# opaq_n1.net
KiCad netlist of a schematic drawn in EAGLE
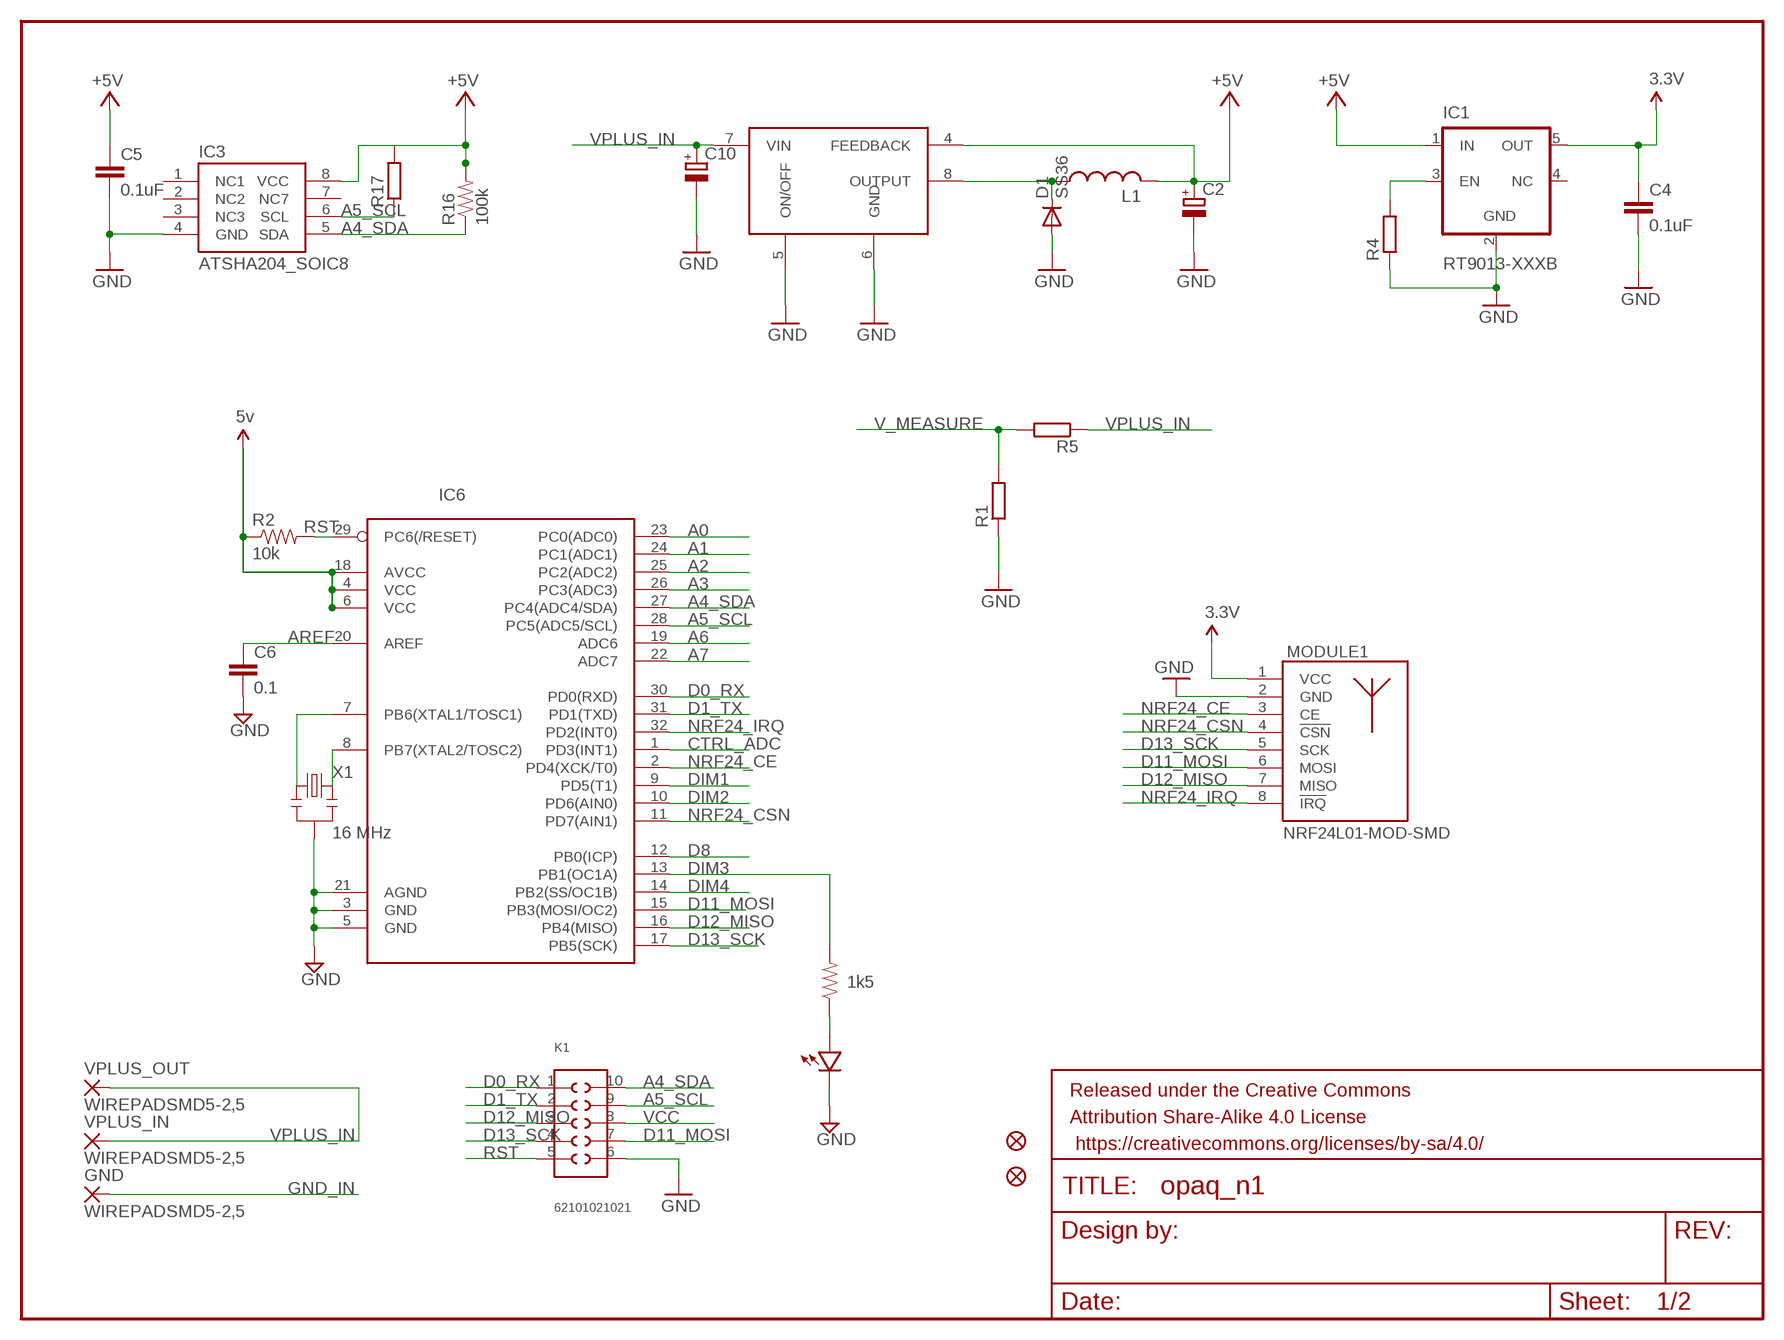
[diagram p0: schematic, sheet 1]
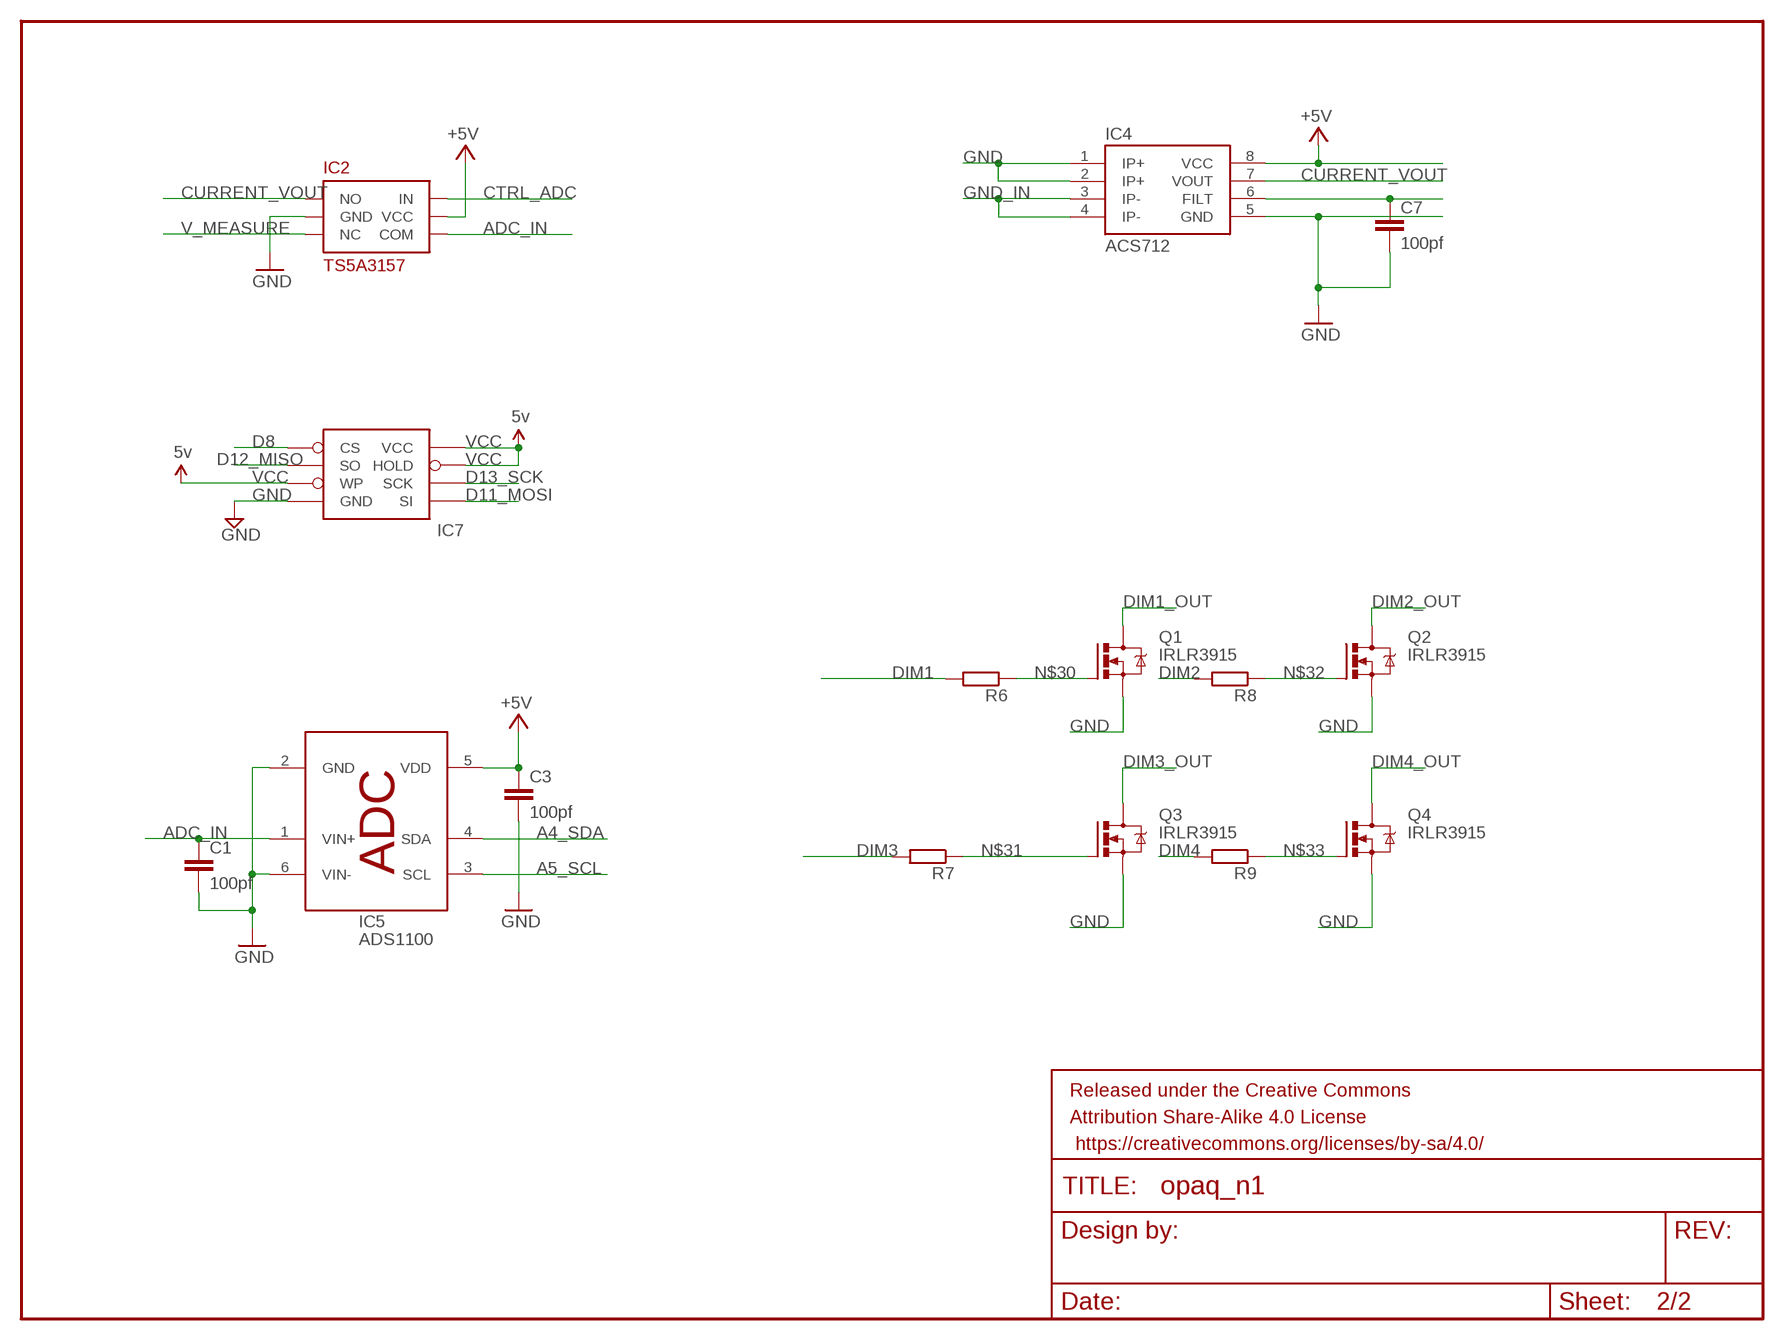
[diagram p1: schematic, sheet 2]

(export (version "E")
  (design (tool "Eeschema 10.0.6"))
  (components
    (comp (ref "C1")
      (value "100pf")
      (footprint "eagle-import:0402-CAP")
      (libsource (lib "eagle-import") (part "SparkFun-Passives_CAP0402-CAP"))
    )
    (comp (ref "C3")
      (value "100pf")
      (footprint "eagle-import:0402-CAP")
      (libsource (lib "eagle-import") (part "SparkFun-Passives_CAP0402-CAP"))
    )
    (comp (ref "C7")
      (value "100pf")
      (footprint "eagle-import:0402-CAP")
      (libsource (lib "eagle-import") (part "SparkFun-Passives_CAP0402-CAP"))
    )
    (comp (ref "FRAME2")
      (value "FRAME-LETTERNO_PACKAGE")
      (footprint "eagle-import:DUMMY")
      (fields (field (name "DESIGNER") "Nobody"))
      (libsource (lib "eagle-import") (part "FRAME-LETTERNO_PACKAGE"))
    )
    (comp (ref "IC2")
      (value "TS5A3157")
      (footprint "eagle-import:SOT23-6")
      (libsource (lib "eagle-import") (part "TS5A3157"))
    )
    (comp (ref "IC4")
      (value "ACS712")
      (footprint "eagle-import:SO08")
      (libsource (lib "eagle-import") (part "ACS712"))
    )
    (comp (ref "IC5")
      (value "ADS1100")
      (footprint "eagle-import:SOT23-6")
      (fields (field (name "MF") "TI"))
      (libsource (lib "eagle-import") (part "ADS1100"))
    )
    (comp (ref "IC7")
      (value "AT25F512BWIDE_5.3MM")
      (footprint "eagle-import:SO08WIDE")
      (libsource (lib "eagle-import") (part "AT25F512BWIDE_5.3MM"))
    )
    (comp (ref "Q1")
      (value "IRLR3915")
      (footprint "eagle-import:D-PAK_TO252AA")
      (libsource (lib "eagle-import") (part "IRLR3915"))
    )
    (comp (ref "Q2")
      (value "IRLR3915")
      (footprint "eagle-import:D-PAK_TO252AA")
      (libsource (lib "eagle-import") (part "IRLR3915"))
    )
    (comp (ref "Q3")
      (value "IRLR3915")
      (footprint "eagle-import:D-PAK_TO252AA")
      (libsource (lib "eagle-import") (part "IRLR3915"))
    )
    (comp (ref "Q4")
      (value "IRLR3915")
      (footprint "eagle-import:D-PAK_TO252AA")
      (libsource (lib "eagle-import") (part "IRLR3915"))
    )
    (comp (ref "R6")
      (value "R-EU_R0805")
      (footprint "eagle-import:0805")
      (libsource (lib "eagle-import") (part "R-EU_R0805"))
    )
    (comp (ref "R7")
      (value "R-EU_R0805")
      (footprint "eagle-import:0805")
      (libsource (lib "eagle-import") (part "R-EU_R0805"))
    )
    (comp (ref "R8")
      (value "R-EU_R0805")
      (footprint "eagle-import:0805")
      (libsource (lib "eagle-import") (part "R-EU_R0805"))
    )
    (comp (ref "R9")
      (value "R-EU_R0805")
      (footprint "eagle-import:0805")
      (libsource (lib "eagle-import") (part "R-EU_R0805"))
    )
    (comp (ref "C2")
      (value "CPOL-EUC/6032-28R")
      (footprint "eagle-import:C_6032-28R")
      (libsource (lib "eagle-import") (part "CPOL-EUC/6032-28R"))
    )
    (comp (ref "C4")
      (value "0.1uF")
      (footprint "eagle-import:0805")
      (libsource (lib "eagle-import") (part "SparkFun-Passives_CAP0805"))
    )
    (comp (ref "C5")
      (value "0.1uF")
      (footprint "eagle-import:0805")
      (libsource (lib "eagle-import") (part "SparkFun-Passives_CAP0805"))
    )
    (comp (ref "C6")
      (value "0.1")
      (footprint "eagle-import:0603-CAP")
      (libsource (lib "eagle-import") (part "CAP0603-CAP"))
    )
    (comp (ref "C10")
      (value "CPOL-EUD/7343-31R")
      (footprint "eagle-import:D_7343-31R")
      (libsource (lib "eagle-import") (part "CPOL-EUD/7343-31R"))
    )
    (comp (ref "D1")
      (value "SS36")
      (footprint "eagle-import:SMA-DIODE")
      (libsource (lib "eagle-import") (part "DIODESMA"))
    )
    (comp (ref "DIM")
      (value "LED0603")
      (footprint "eagle-import:0603-LED")
      (libsource (lib "eagle-import") (part "LED0603"))
    )
    (comp (ref "FRAME1")
      (value "FRAME-LETTER")
      (footprint "eagle-import:CREATIVE_COMMONS")
      (libsource (lib "eagle-import") (part "FRAME-LETTER"))
    )
    (comp (ref "GND")
      (value "WIREPADSMD5-2,5")
      (footprint "eagle-import:5-2,5")
      (libsource (lib "eagle-import") (part "WIREPADSMD5-2,5"))
    )
    (comp (ref "IC1")
      (value "RT9013-XXXB")
      (footprint "eagle-import:SOT23-5")
      (libsource (lib "eagle-import") (part "RT9013-XXXB"))
    )
    (comp (ref "IC3")
      (value "ATSHA204_SOIC8")
      (footprint "eagle-import:SOIC8")
      (libsource (lib "eagle-import") (part "ATSHA204_SOIC8"))
    )
    (comp (ref "IC6")
      (value "ATMega-328")
      (footprint "eagle-import:MLF32")
      (libsource (lib "eagle-import") (part "ATMEGA168/328MLF"))
    )
    (comp (ref "IC8")
      (value "LM2594HV")
      (footprint "eagle-import:SO08")
      (libsource (lib "eagle-import") (part "LM2594"))
    )
    (comp (ref "JP1")
      (value "FIDUCIAL1X2.5")
      (footprint "eagle-import:FIDUCIAL-1X2.5")
      (libsource (lib "eagle-import") (part "FIDUCIAL1X2.5"))
    )
    (comp (ref "JP2")
      (value "FIDUCIAL1X2.5")
      (footprint "eagle-import:FIDUCIAL-1X2.5")
      (libsource (lib "eagle-import") (part "FIDUCIAL1X2.5"))
    )
    (comp (ref "K1")
      (value "62101021021")
      (footprint "eagle-import:62101021021")
      (libsource (lib "eagle-import") (part "62101021021"))
    )
    (comp (ref "L1")
      (value "NR6045")
      (footprint "eagle-import:2525")
      (libsource (lib "eagle-import") (part "NR6045"))
    )
    (comp (ref "MODULE1")
      (value "NRF24L01-MOD-SMD")
      (footprint "eagle-import:SMD8-MODULE")
      (libsource (lib "eagle-import") (part "NRF24L01-MOD-SMD"))
    )
    (comp (ref "R1")
      (value "R-EU_R0805")
      (footprint "eagle-import:0805")
      (libsource (lib "eagle-import") (part "R-EU_R0805"))
    )
    (comp (ref "R2")
      (value "10k")
      (footprint "eagle-import:0603-RES")
      (libsource (lib "eagle-import") (part "RESISTOR0603-RES"))
    )
    (comp (ref "R3")
      (value "1k5")
      (footprint "eagle-import:0603-RES")
      (libsource (lib "eagle-import") (part "RESISTOR0603-RES"))
    )
    (comp (ref "R4")
      (value "R-EU_R0805")
      (footprint "eagle-import:0805")
      (libsource (lib "eagle-import") (part "R-EU_R0805"))
    )
    (comp (ref "R5")
      (value "R-EU_R0805")
      (footprint "eagle-import:0805")
      (libsource (lib "eagle-import") (part "R-EU_R0805"))
    )
    (comp (ref "R16")
      (value "100k")
      (footprint "eagle-import:0805")
      (libsource (lib "eagle-import") (part "SparkFun-Passives_RESISTOR0805-RES"))
    )
    (comp (ref "R17")
      (value "R-EU_R0805")
      (footprint "eagle-import:0805")
      (libsource (lib "eagle-import") (part "R-EU_R0805"))
    )
    (comp (ref "VPLUS_IN")
      (value "WIREPADSMD5-2,5")
      (footprint "eagle-import:5-2,5")
      (libsource (lib "eagle-import") (part "WIREPADSMD5-2,5"))
    )
    (comp (ref "VPLUS_OUT")
      (value "WIREPADSMD5-2,5")
      (footprint "eagle-import:5-2,5")
      (libsource (lib "eagle-import") (part "WIREPADSMD5-2,5"))
    )
    (comp (ref "X1")
      (value "16 MHz")
      (footprint "eagle-import:RESONATOR-SMD")
      (libsource (lib "eagle-import") (part "RESONATORSMD"))
    )
  )
  (nets
    (net (code "1") (name "+5V") (class "Default")
      (node (ref "C2") (pin "+") (pinfunction "+_+") (pintype "passive"))
      (node (ref "C3") (pin "1") (pinfunction "1_1") (pintype "passive"))
      (node (ref "C5") (pin "1") (pinfunction "1_1") (pintype "passive"))
      (node (ref "IC1") (pin "1") (pinfunction "IN_1") (pintype "input"))
      (node (ref "IC2") (pin "5") (pinfunction "VCC_5") (pintype "bidirectional"))
      (node (ref "IC3") (pin "8") (pinfunction "VCC_8") (pintype "power_in"))
      (node (ref "IC4") (pin "8") (pinfunction "VCC_8") (pintype "bidirectional"))
      (node (ref "IC5") (pin "5") (pinfunction "VDD_5") (pintype "power_in"))
      (node (ref "IC8") (pin "4") (pinfunction "FEEDBACK_4") (pintype "bidirectional"))
      (node (ref "L1") (pin "P$1") (pinfunction "P$1_P$1") (pintype "passive"))
      (node (ref "R16") (pin "2") (pinfunction "2_2") (pintype "passive"))
      (node (ref "R17") (pin "2") (pinfunction "2_2") (pintype "passive"))
    )
    (net (code "2") (name "3.3V") (class "Default")
      (node (ref "C4") (pin "1") (pinfunction "1_1") (pintype "passive"))
      (node (ref "IC1") (pin "5") (pinfunction "OUT_5") (pintype "passive"))
      (node (ref "MODULE1") (pin "1") (pinfunction "VCC_1") (pintype "power_in"))
    )
    (net (code "3") (name "A0") (class "Default")
      (node (ref "IC6") (pin "23") (pinfunction "PC0(ADC0)_23") (pintype "bidirectional"))
    )
    (net (code "4") (name "A1") (class "Default")
      (node (ref "IC6") (pin "24") (pinfunction "PC1(ADC1)_24") (pintype "bidirectional"))
    )
    (net (code "5") (name "A2") (class "Default")
      (node (ref "IC6") (pin "25") (pinfunction "PC2(ADC2)_25") (pintype "bidirectional"))
    )
    (net (code "6") (name "A3") (class "Default")
      (node (ref "IC6") (pin "26") (pinfunction "PC3(ADC3)_26") (pintype "bidirectional"))
    )
    (net (code "7") (name "A4_SDA") (class "Default")
      (node (ref "IC3") (pin "5") (pinfunction "SDA_5") (pintype "bidirectional"))
      (node (ref "IC5") (pin "4") (pinfunction "SDA_4") (pintype "bidirectional"))
      (node (ref "IC6") (pin "27") (pinfunction "PC4(ADC4/SDA)_27") (pintype "bidirectional"))
      (node (ref "K1") (pin "10") (pinfunction "10_10") (pintype "passive"))
      (node (ref "R16") (pin "1") (pinfunction "1_1") (pintype "passive"))
    )
    (net (code "8") (name "A5_SCL") (class "Default")
      (node (ref "IC3") (pin "6") (pinfunction "SCL_6") (pintype "bidirectional"))
      (node (ref "IC5") (pin "3") (pinfunction "SCL_3") (pintype "input"))
      (node (ref "IC6") (pin "28") (pinfunction "PC5(ADC5/SCL)_28") (pintype "bidirectional"))
      (node (ref "K1") (pin "9") (pinfunction "9_9") (pintype "passive"))
      (node (ref "R17") (pin "1") (pinfunction "1_1") (pintype "passive"))
    )
    (net (code "9") (name "A6") (class "Default")
      (node (ref "IC6") (pin "19") (pinfunction "ADC6_19") (pintype "bidirectional"))
    )
    (net (code "10") (name "A7") (class "Default")
      (node (ref "IC6") (pin "22") (pinfunction "ADC7_22") (pintype "bidirectional"))
    )
    (net (code "11") (name "ADC_IN") (class "Default")
      (node (ref "C1") (pin "1") (pinfunction "1_1") (pintype "passive"))
      (node (ref "IC2") (pin "4") (pinfunction "COM_4") (pintype "bidirectional"))
      (node (ref "IC5") (pin "1") (pinfunction "VIN+_1") (pintype "input"))
    )
    (net (code "12") (name "AREF") (class "Default")
      (node (ref "C6") (pin "1") (pinfunction "1_1") (pintype "passive"))
      (node (ref "IC6") (pin "20") (pinfunction "AREF_20") (pintype "bidirectional"))
    )
    (net (code "13") (name "CTRL_ADC") (class "Default")
      (node (ref "IC2") (pin "6") (pinfunction "IN_6") (pintype "bidirectional"))
      (node (ref "IC6") (pin "1") (pinfunction "PD3(INT1)_1") (pintype "bidirectional"))
    )
    (net (code "14") (name "CURRENT_VOUT") (class "Default")
      (node (ref "IC2") (pin "1") (pinfunction "NO_1") (pintype "bidirectional"))
      (node (ref "IC4") (pin "7") (pinfunction "VOUT_7") (pintype "bidirectional"))
    )
    (net (code "15") (name "D0_RX") (class "Default")
      (node (ref "IC6") (pin "30") (pinfunction "PD0(RXD)_30") (pintype "bidirectional"))
      (node (ref "K1") (pin "1") (pinfunction "1_1") (pintype "passive"))
    )
    (net (code "16") (name "D1_TX") (class "Default")
      (node (ref "IC6") (pin "31") (pinfunction "PD1(TXD)_31") (pintype "bidirectional"))
      (node (ref "K1") (pin "2") (pinfunction "2_2") (pintype "passive"))
    )
    (net (code "17") (name "D8") (class "Default")
      (node (ref "IC6") (pin "12") (pinfunction "PB0(ICP)_12") (pintype "bidirectional"))
      (node (ref "IC7") (pin "1") (pinfunction "CS_1") (pintype "bidirectional"))
    )
    (net (code "18") (name "D11_MOSI") (class "Default")
      (node (ref "IC6") (pin "15") (pinfunction "PB3(MOSI/OC2)_15") (pintype "bidirectional"))
      (node (ref "IC7") (pin "5") (pinfunction "SI_5") (pintype "bidirectional"))
      (node (ref "K1") (pin "7") (pinfunction "7_7") (pintype "passive"))
      (node (ref "MODULE1") (pin "6") (pinfunction "MOSI_6") (pintype "input"))
    )
    (net (code "19") (name "D12_MISO") (class "Default")
      (node (ref "IC6") (pin "16") (pinfunction "PB4(MISO)_16") (pintype "bidirectional"))
      (node (ref "IC7") (pin "2") (pinfunction "SO_2") (pintype "bidirectional"))
      (node (ref "K1") (pin "3") (pinfunction "3_3") (pintype "passive"))
      (node (ref "MODULE1") (pin "7") (pinfunction "MISO_7") (pintype "output"))
    )
    (net (code "20") (name "D13_SCK") (class "Default")
      (node (ref "IC6") (pin "17") (pinfunction "PB5(SCK)_17") (pintype "bidirectional"))
      (node (ref "IC7") (pin "6") (pinfunction "SCK_6") (pintype "bidirectional"))
      (node (ref "K1") (pin "4") (pinfunction "4_4") (pintype "passive"))
      (node (ref "MODULE1") (pin "5") (pinfunction "SCK_5") (pintype "input"))
    )
    (net (code "21") (name "DIM1") (class "Default")
      (node (ref "IC6") (pin "9") (pinfunction "PD5(T1)_9") (pintype "bidirectional"))
      (node (ref "R6") (pin "2") (pinfunction "2_2") (pintype "passive"))
    )
    (net (code "22") (name "DIM1_OUT") (class "Default")
      (node (ref "Q1") (pin "4") (pinfunction "D_4") (pintype "passive"))
    )
    (net (code "23") (name "DIM2") (class "Default")
      (node (ref "IC6") (pin "10") (pinfunction "PD6(AIN0)_10") (pintype "bidirectional"))
      (node (ref "R8") (pin "2") (pinfunction "2_2") (pintype "passive"))
    )
    (net (code "24") (name "DIM2_OUT") (class "Default")
      (node (ref "Q2") (pin "4") (pinfunction "D_4") (pintype "passive"))
    )
    (net (code "25") (name "DIM3") (class "Default")
      (node (ref "IC6") (pin "13") (pinfunction "PB1(OC1A)_13") (pintype "bidirectional"))
      (node (ref "R3") (pin "2") (pinfunction "2_2") (pintype "passive"))
      (node (ref "R7") (pin "2") (pinfunction "2_2") (pintype "passive"))
    )
    (net (code "26") (name "DIM3_OUT") (class "Default")
      (node (ref "Q3") (pin "4") (pinfunction "D_4") (pintype "passive"))
    )
    (net (code "27") (name "DIM4") (class "Default")
      (node (ref "IC6") (pin "14") (pinfunction "PB2(SS/OC1B)_14") (pintype "bidirectional"))
      (node (ref "R9") (pin "2") (pinfunction "2_2") (pintype "passive"))
    )
    (net (code "28") (name "DIM4_OUT") (class "Default")
      (node (ref "Q4") (pin "4") (pinfunction "D_4") (pintype "passive"))
    )
    (net (code "29") (name "GND") (class "Default")
      (node (ref "C1") (pin "2") (pinfunction "2_2") (pintype "passive"))
      (node (ref "C10") (pin "-") (pinfunction "-_-") (pintype "passive"))
      (node (ref "C2") (pin "-") (pinfunction "-_-") (pintype "passive"))
      (node (ref "C3") (pin "2") (pinfunction "2_2") (pintype "passive"))
      (node (ref "C4") (pin "2") (pinfunction "2_2") (pintype "passive"))
      (node (ref "C5") (pin "2") (pinfunction "2_2") (pintype "passive"))
      (node (ref "C6") (pin "2") (pinfunction "2_2") (pintype "passive"))
      (node (ref "C7") (pin "2") (pinfunction "2_2") (pintype "passive"))
      (node (ref "D1") (pin "A") (pinfunction "A_A") (pintype "passive"))
      (node (ref "DIM") (pin "MINUS") (pinfunction "MINUS_MINUS") (pintype "passive"))
      (node (ref "IC1") (pin "2") (pinfunction "GND_2") (pintype "power_in"))
      (node (ref "IC2") (pin "2") (pinfunction "GND_2") (pintype "bidirectional"))
      (node (ref "IC3") (pin "4") (pinfunction "GND_4") (pintype "power_in"))
      (node (ref "IC4") (pin "1") (pinfunction "IP+_1") (pintype "bidirectional"))
      (node (ref "IC4") (pin "2") (pinfunction "IP+_2") (pintype "bidirectional"))
      (node (ref "IC4") (pin "5") (pinfunction "GND_5") (pintype "bidirectional"))
      (node (ref "IC5") (pin "2") (pinfunction "GND_2") (pintype "power_in"))
      (node (ref "IC5") (pin "6") (pinfunction "VIN-_6") (pintype "input"))
      (node (ref "IC6") (pin "21") (pinfunction "AGND_21") (pintype "bidirectional"))
      (node (ref "IC6") (pin "3") (pinfunction "GND_3") (pintype "bidirectional"))
      (node (ref "IC6") (pin "5") (pinfunction "GND_5") (pintype "bidirectional"))
      (node (ref "IC7") (pin "4") (pinfunction "GND_4") (pintype "bidirectional"))
      (node (ref "IC8") (pin "5") (pinfunction "ON/OFF_5") (pintype "bidirectional"))
      (node (ref "IC8") (pin "6") (pinfunction "GND_6") (pintype "bidirectional"))
      (node (ref "K1") (pin "6") (pinfunction "6_6") (pintype "passive"))
      (node (ref "MODULE1") (pin "2") (pinfunction "GND_2") (pintype "power_in"))
      (node (ref "Q1") (pin "3") (pinfunction "S_3") (pintype "passive"))
      (node (ref "Q2") (pin "3") (pinfunction "S_3") (pintype "passive"))
      (node (ref "Q3") (pin "3") (pinfunction "S_3") (pintype "passive"))
      (node (ref "Q4") (pin "3") (pinfunction "S_3") (pintype "passive"))
      (node (ref "R1") (pin "1") (pinfunction "1_1") (pintype "passive"))
      (node (ref "R4") (pin "1") (pinfunction "1_1") (pintype "passive"))
      (node (ref "X1") (pin "2") (pinfunction "2_2") (pintype "passive"))
    )
    (net (code "30") (name "GND_IN") (class "Default")
      (node (ref "GND") (pin "1") (pinfunction "P_1") (pintype "passive"))
      (node (ref "IC4") (pin "3") (pinfunction "IP-_3") (pintype "bidirectional"))
      (node (ref "IC4") (pin "4") (pinfunction "IP-_4") (pintype "bidirectional"))
    )
    (net (code "31") (name "N$30") (class "Default")
      (node (ref "Q1") (pin "1") (pinfunction "G_1") (pintype "passive"))
      (node (ref "R6") (pin "1") (pinfunction "1_1") (pintype "passive"))
    )
    (net (code "32") (name "N$31") (class "Default")
      (node (ref "Q3") (pin "1") (pinfunction "G_1") (pintype "passive"))
      (node (ref "R7") (pin "1") (pinfunction "1_1") (pintype "passive"))
    )
    (net (code "33") (name "N$32") (class "Default")
      (node (ref "Q2") (pin "1") (pinfunction "G_1") (pintype "passive"))
      (node (ref "R8") (pin "1") (pinfunction "1_1") (pintype "passive"))
    )
    (net (code "34") (name "N$33") (class "Default")
      (node (ref "Q4") (pin "1") (pinfunction "G_1") (pintype "passive"))
      (node (ref "R9") (pin "1") (pinfunction "1_1") (pintype "passive"))
    )
    (net (code "35") (name "NRF24_CE") (class "Default")
      (node (ref "IC6") (pin "2") (pinfunction "PD4(XCK/T0)_2") (pintype "bidirectional"))
      (node (ref "MODULE1") (pin "3") (pinfunction "CE_3") (pintype "input"))
    )
    (net (code "36") (name "NRF24_CSN") (class "Default")
      (node (ref "IC6") (pin "11") (pinfunction "PD7(AIN1)_11") (pintype "bidirectional"))
      (node (ref "MODULE1") (pin "4") (pinfunction "~{CSN}_4") (pintype "input"))
    )
    (net (code "37") (name "NRF24_IRQ") (class "Default")
      (node (ref "IC6") (pin "32") (pinfunction "PD2(INT0)_32") (pintype "bidirectional"))
      (node (ref "MODULE1") (pin "8") (pinfunction "~{IRQ}_8") (pintype "open_collector"))
    )
    (net (code "38") (name "Net-(DIM-PadPLUS)") (class "Default")
      (node (ref "DIM") (pin "PLUS") (pinfunction "PLUS_PLUS") (pintype "passive"))
      (node (ref "R3") (pin "1") (pinfunction "1_1") (pintype "passive"))
    )
    (net (code "39") (name "Net-(IC1-EN)") (class "Default")
      (node (ref "IC1") (pin "3") (pinfunction "EN_3") (pintype "input"))
      (node (ref "R4") (pin "2") (pinfunction "2_2") (pintype "passive"))
    )
    (net (code "40") (name "Net-(IC4-FILT)") (class "Default")
      (node (ref "C7") (pin "1") (pinfunction "1_1") (pintype "passive"))
      (node (ref "IC4") (pin "6") (pinfunction "FILT_6") (pintype "bidirectional"))
    )
    (net (code "41") (name "Net-(IC6-PB6(XTAL1{slash}TOSC1))") (class "Default")
      (node (ref "IC6") (pin "7") (pinfunction "PB6(XTAL1/TOSC1)_7") (pintype "bidirectional"))
      (node (ref "X1") (pin "1") (pinfunction "1_1") (pintype "passive"))
    )
    (net (code "42") (name "Net-(IC6-PB7(XTAL2{slash}TOSC2))") (class "Default")
      (node (ref "IC6") (pin "8") (pinfunction "PB7(XTAL2/TOSC2)_8") (pintype "bidirectional"))
      (node (ref "X1") (pin "3") (pinfunction "3_3") (pintype "passive"))
    )
    (net (code "43") (name "Net-(IC8-OUTPUT)") (class "Default")
      (node (ref "D1") (pin "C") (pinfunction "C_C") (pintype "passive"))
      (node (ref "IC8") (pin "8") (pinfunction "OUTPUT_8") (pintype "bidirectional"))
      (node (ref "L1") (pin "P$2") (pinfunction "P$2_P$2") (pintype "passive"))
    )
    (net (code "44") (name "RST") (class "Default")
      (node (ref "IC6") (pin "29") (pinfunction "PC6(/RESET)_29") (pintype "bidirectional"))
      (node (ref "K1") (pin "5") (pinfunction "5_5") (pintype "passive"))
      (node (ref "R2") (pin "2") (pinfunction "2_2") (pintype "passive"))
    )
    (net (code "45") (name "VCC") (class "Default")
      (node (ref "IC6") (pin "18") (pinfunction "AVCC_18") (pintype "bidirectional"))
      (node (ref "IC6") (pin "4") (pinfunction "VCC_4") (pintype "bidirectional"))
      (node (ref "IC6") (pin "6") (pinfunction "VCC_6") (pintype "bidirectional"))
      (node (ref "IC7") (pin "3") (pinfunction "WP_3") (pintype "bidirectional"))
      (node (ref "IC7") (pin "7") (pinfunction "HOLD_7") (pintype "bidirectional"))
      (node (ref "IC7") (pin "8") (pinfunction "VCC_8") (pintype "bidirectional"))
      (node (ref "K1") (pin "8") (pinfunction "8_8") (pintype "passive"))
      (node (ref "R2") (pin "1") (pinfunction "1_1") (pintype "passive"))
    )
    (net (code "46") (name "VPLUS_IN") (class "Default")
      (node (ref "C10") (pin "+") (pinfunction "+_+") (pintype "passive"))
      (node (ref "IC8") (pin "7") (pinfunction "VIN_7") (pintype "bidirectional"))
      (node (ref "R5") (pin "1") (pinfunction "1_1") (pintype "passive"))
      (node (ref "VPLUS_IN") (pin "1") (pinfunction "P_1") (pintype "passive"))
      (node (ref "VPLUS_OUT") (pin "1") (pinfunction "P_1") (pintype "passive"))
    )
    (net (code "47") (name "V_MEASURE") (class "Default")
      (node (ref "IC2") (pin "3") (pinfunction "NC_3") (pintype "bidirectional"))
      (node (ref "R1") (pin "2") (pinfunction "2_2") (pintype "passive"))
      (node (ref "R5") (pin "2") (pinfunction "2_2") (pintype "passive"))
    )
    (net (code "48") (name "unconnected-(IC1-NC-Pad4)") (class "Default")
      (node (ref "IC1") (pin "4") (pinfunction "NC_4") (pintype "no_connect"))
    )
    (net (code "49") (name "unconnected-(IC3-NC1-Pad1)") (class "Default")
      (node (ref "IC3") (pin "1") (pinfunction "NC1_1") (pintype "no_connect"))
    )
    (net (code "50") (name "unconnected-(IC3-NC2-Pad2)") (class "Default")
      (node (ref "IC3") (pin "2") (pinfunction "NC2_2") (pintype "no_connect"))
    )
    (net (code "51") (name "unconnected-(IC3-NC3-Pad3)") (class "Default")
      (node (ref "IC3") (pin "3") (pinfunction "NC3_3") (pintype "no_connect"))
    )
    (net (code "52") (name "unconnected-(IC3-NC7-Pad7)") (class "Default")
      (node (ref "IC3") (pin "7") (pinfunction "NC7_7") (pintype "no_connect"))
    )
  )
)
